# Lightpack_6_0T_man.net
KiCad netlist of a schematic drawn in EAGLE
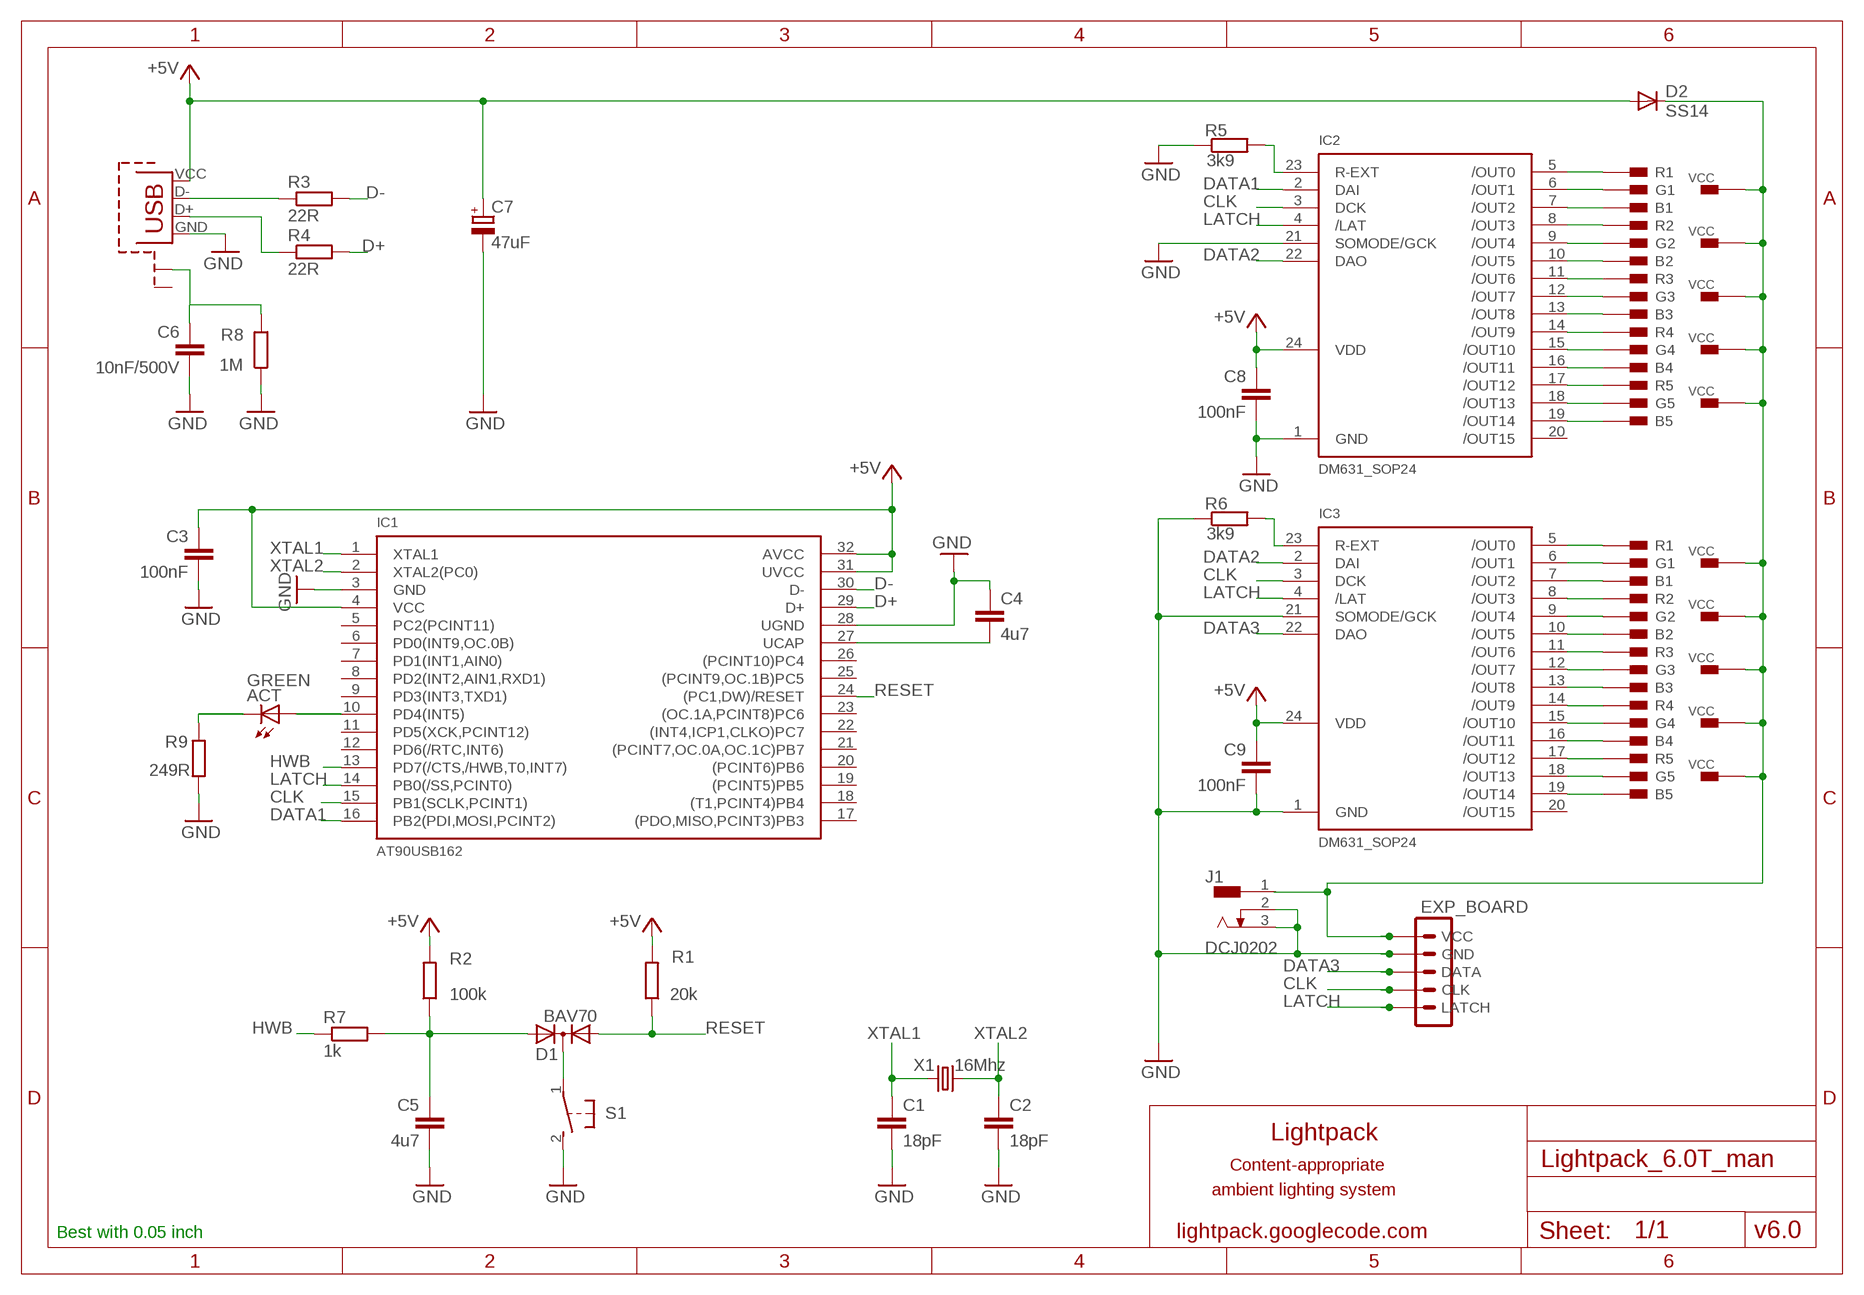
[diagram p0: schematic, sheet 1]

(export (version "E")
  (design (tool "Eeschema 10.0.6"))
  (components
    (comp (ref "ACT")
      (value "GREEN")
      (footprint "eagle-import:LED3MM")
      (libsource (lib "eagle-import") (part "LED3MM"))
    )
    (comp (ref "C1")
      (value "18pF")
      (footprint "eagle-import:C0805")
      (libsource (lib "eagle-import") (part "C-EUC0805"))
    )
    (comp (ref "C2")
      (value "18pF")
      (footprint "eagle-import:C0805")
      (libsource (lib "eagle-import") (part "C-EUC0805"))
    )
    (comp (ref "C3")
      (value "100nF")
      (footprint "eagle-import:C0805")
      (libsource (lib "eagle-import") (part "C-EUC0805"))
    )
    (comp (ref "C4")
      (value "4u7")
      (footprint "eagle-import:C0805")
      (libsource (lib "eagle-import") (part "C-EUC0805"))
    )
    (comp (ref "C5")
      (value "4u7")
      (footprint "eagle-import:C0805")
      (libsource (lib "eagle-import") (part "C-EUC0805"))
    )
    (comp (ref "C6")
      (value "10nF/500V")
      (footprint "eagle-import:C0805")
      (libsource (lib "eagle-import") (part "C-EUC0805"))
    )
    (comp (ref "C7")
      (value "47uF")
      (footprint "eagle-import:SMC_D")
      (libsource (lib "eagle-import") (part "CPOL-EUSMCD"))
    )
    (comp (ref "C8")
      (value "100nF")
      (footprint "eagle-import:C0805")
      (libsource (lib "eagle-import") (part "C-EUC0805"))
    )
    (comp (ref "C9")
      (value "100nF")
      (footprint "eagle-import:C0805")
      (libsource (lib "eagle-import") (part "C-EUC0805"))
    )
    (comp (ref "CN1")
      (value "USB-MICRO-B-EVT")
      (footprint "eagle-import:USB-MICRO-B-UNIVERSAL-SOLID-FOOTS")
      (libsource (lib "eagle-import") (part "USB-MICRO-B-EVT"))
    )
    (comp (ref "CN2")
      (value "RJ11-5P-REEL-LIGHTPACK6T2")
      (footprint "eagle-import:RJ11-1XN-5P")
      (libsource (lib "eagle-import") (part "RJ11-5P-REEL-LIGHTPACK6T2"))
    )
    (comp (ref "CN3")
      (value "RJ11-5P-REEL-MAIN")
      (footprint "eagle-import:RJ11-1XN-5P")
      (libsource (lib "eagle-import") (part "RJ11-5P-REEL-MAIN"))
    )
    (comp (ref "D1")
      (value "BAV70")
      (footprint "eagle-import:SOT23")
      (libsource (lib "eagle-import") (part "DIODE-2AC|CASOT23"))
    )
    (comp (ref "D2")
      (value "SS14")
      (footprint "eagle-import:SMB")
      (libsource (lib "eagle-import") (part "DIODE-SMB"))
    )
    (comp (ref "EXP_BOARD")
      (value "MA05-1")
      (footprint "eagle-import:MA05-1")
      (libsource (lib "eagle-import") (part "MA05-1"))
    )
    (comp (ref "IC1")
      (value "AT90USB162")
      (footprint "eagle-import:TQFP32")
      (libsource (lib "eagle-import") (part "AT90USB162"))
    )
    (comp (ref "IC2")
      (value "DM631_SOP24")
      (footprint "eagle-import:SOP24-300-1.27")
      (libsource (lib "eagle-import") (part "DM631_SOP24"))
    )
    (comp (ref "IC3")
      (value "DM631_SOP24")
      (footprint "eagle-import:SOP24-300-1.27")
      (libsource (lib "eagle-import") (part "DM631_SOP24"))
    )
    (comp (ref "J1")
      (value "DCJ0202")
      (footprint "eagle-import:DCJ0202")
      (libsource (lib "eagle-import") (part "DCJ0202"))
    )
    (comp (ref "R1")
      (value "20k")
      (footprint "eagle-import:R0805")
      (libsource (lib "eagle-import") (part "R-EU_R0805"))
    )
    (comp (ref "R2")
      (value "100k")
      (footprint "eagle-import:R0805")
      (libsource (lib "eagle-import") (part "R-EU_R0805"))
    )
    (comp (ref "R3")
      (value "22R")
      (footprint "eagle-import:R0805")
      (libsource (lib "eagle-import") (part "R-EU_R0805"))
    )
    (comp (ref "R4")
      (value "22R")
      (footprint "eagle-import:R0805")
      (libsource (lib "eagle-import") (part "R-EU_R0805"))
    )
    (comp (ref "R5")
      (value "3k9")
      (footprint "eagle-import:R0805")
      (libsource (lib "eagle-import") (part "R-EU_R0805"))
    )
    (comp (ref "R6")
      (value "3k9")
      (footprint "eagle-import:R0805")
      (libsource (lib "eagle-import") (part "R-EU_R0805"))
    )
    (comp (ref "R7")
      (value "1k")
      (footprint "eagle-import:R0805")
      (libsource (lib "eagle-import") (part "R-EU_R0805"))
    )
    (comp (ref "R8")
      (value "1M")
      (footprint "eagle-import:R0805")
      (libsource (lib "eagle-import") (part "R-EU_R0805"))
    )
    (comp (ref "R9")
      (value "249R")
      (footprint "eagle-import:R0805")
      (libsource (lib "eagle-import") (part "R-EU_R0805"))
    )
    (comp (ref "S1")
      (value "31-XX")
      (footprint "eagle-import:B3F-31XX")
      (libsource (lib "eagle-import") (part "31-XX"))
    )
    (comp (ref "X1")
      (value "16Mhz")
      (footprint "eagle-import:HC49UP")
      (libsource (lib "eagle-import") (part "CRYSTALHC49UP"))
    )
  )
  (nets
    (net (code "1") (name "+5V") (class "Default")
      (node (ref "C3") (pin "1") (pinfunction "1_1") (pintype "passive"))
      (node (ref "C7") (pin "+") (pinfunction "+_+") (pintype "passive"))
      (node (ref "C8") (pin "1") (pinfunction "1_1") (pintype "passive"))
      (node (ref "C9") (pin "1") (pinfunction "1_1") (pintype "passive"))
      (node (ref "CN1") (pin "VCC") (pinfunction "VBUS_VCC") (pintype "bidirectional"))
      (node (ref "D2") (pin "A") (pinfunction "A_A") (pintype "passive"))
      (node (ref "IC1") (pin "31") (pinfunction "UVCC_31") (pintype "bidirectional"))
      (node (ref "IC1") (pin "32") (pinfunction "AVCC_32") (pintype "bidirectional"))
      (node (ref "IC1") (pin "4") (pinfunction "VCC_4") (pintype "bidirectional"))
      (node (ref "IC2") (pin "24") (pinfunction "VDD_24") (pintype "bidirectional"))
      (node (ref "IC3") (pin "24") (pinfunction "VDD_24") (pintype "bidirectional"))
      (node (ref "R1") (pin "2") (pinfunction "2_2") (pintype "passive"))
      (node (ref "R2") (pin "2") (pinfunction "2_2") (pintype "passive"))
    )
    (net (code "2") (name "/CLK") (class "Default")
      (node (ref "EXP_BOARD") (pin "2") (pinfunction "CLK_2") (pintype "passive"))
      (node (ref "IC1") (pin "15") (pinfunction "PB1(SCLK,PCINT1)_15") (pintype "bidirectional"))
      (node (ref "IC2") (pin "3") (pinfunction "DCK_3") (pintype "bidirectional"))
      (node (ref "IC3") (pin "3") (pinfunction "DCK_3") (pintype "bidirectional"))
    )
    (net (code "3") (name "/D+") (class "Default")
      (node (ref "IC1") (pin "29") (pinfunction "D+_29") (pintype "bidirectional"))
      (node (ref "R4") (pin "2") (pinfunction "2_2") (pintype "passive"))
    )
    (net (code "4") (name "/D-") (class "Default")
      (node (ref "IC1") (pin "30") (pinfunction "D-_30") (pintype "bidirectional"))
      (node (ref "R3") (pin "2") (pinfunction "2_2") (pintype "passive"))
    )
    (net (code "5") (name "/DATA1") (class "Default")
      (node (ref "IC1") (pin "16") (pinfunction "PB2(PDI,MOSI,PCINT2)_16") (pintype "bidirectional"))
      (node (ref "IC2") (pin "2") (pinfunction "DAI_2") (pintype "bidirectional"))
    )
    (net (code "6") (name "/DATA2") (class "Default")
      (node (ref "IC2") (pin "22") (pinfunction "DAO_22") (pintype "bidirectional"))
      (node (ref "IC3") (pin "2") (pinfunction "DAI_2") (pintype "bidirectional"))
    )
    (net (code "7") (name "/DATA3") (class "Default")
      (node (ref "EXP_BOARD") (pin "3") (pinfunction "DATA_3") (pintype "passive"))
      (node (ref "IC3") (pin "22") (pinfunction "DAO_22") (pintype "bidirectional"))
    )
    (net (code "8") (name "/HWB") (class "Default")
      (node (ref "IC1") (pin "13") (pinfunction "PD7(/CTS,/HWB,T0,INT7)_13") (pintype "bidirectional"))
      (node (ref "R7") (pin "1") (pinfunction "1_1") (pintype "passive"))
    )
    (net (code "9") (name "/LATCH") (class "Default")
      (node (ref "EXP_BOARD") (pin "1") (pinfunction "LATCH_1") (pintype "passive"))
      (node (ref "IC1") (pin "14") (pinfunction "PB0(/SS,PCINT0)_14") (pintype "bidirectional"))
      (node (ref "IC2") (pin "4") (pinfunction "/LAT_4") (pintype "bidirectional"))
      (node (ref "IC3") (pin "4") (pinfunction "/LAT_4") (pintype "bidirectional"))
    )
    (net (code "10") (name "/RESET") (class "Default")
      (node (ref "D1") (pin "1") (pinfunction "A1_1") (pintype "passive"))
      (node (ref "IC1") (pin "24") (pinfunction "(PC1,DW)/RESET_24") (pintype "bidirectional"))
      (node (ref "R1") (pin "1") (pinfunction "1_1") (pintype "passive"))
    )
    (net (code "11") (name "/XTAL1") (class "Default")
      (node (ref "C1") (pin "1") (pinfunction "1_1") (pintype "passive"))
      (node (ref "IC1") (pin "1") (pinfunction "XTAL1_1") (pintype "bidirectional"))
      (node (ref "X1") (pin "1") (pinfunction "1_1") (pintype "passive"))
    )
    (net (code "12") (name "/XTAL2") (class "Default")
      (node (ref "C2") (pin "1") (pinfunction "1_1") (pintype "passive"))
      (node (ref "IC1") (pin "2") (pinfunction "XTAL2(PC0)_2") (pintype "bidirectional"))
      (node (ref "X1") (pin "2") (pinfunction "2_2") (pintype "passive"))
    )
    (net (code "13") (name "GND") (class "Default")
      (node (ref "C1") (pin "2") (pinfunction "2_2") (pintype "passive"))
      (node (ref "C2") (pin "2") (pinfunction "2_2") (pintype "passive"))
      (node (ref "C3") (pin "2") (pinfunction "2_2") (pintype "passive"))
      (node (ref "C4") (pin "1") (pinfunction "1_1") (pintype "passive"))
      (node (ref "C5") (pin "2") (pinfunction "2_2") (pintype "passive"))
      (node (ref "C6") (pin "1") (pinfunction "1_1") (pintype "passive"))
      (node (ref "C7") (pin "-") (pinfunction "-_-") (pintype "passive"))
      (node (ref "C8") (pin "2") (pinfunction "2_2") (pintype "passive"))
      (node (ref "C9") (pin "2") (pinfunction "2_2") (pintype "passive"))
      (node (ref "CN1") (pin "GND") (pinfunction "GND_GND") (pintype "bidirectional"))
      (node (ref "EXP_BOARD") (pin "4") (pinfunction "GND_4") (pintype "passive"))
      (node (ref "IC1") (pin "28") (pinfunction "UGND_28") (pintype "bidirectional"))
      (node (ref "IC1") (pin "3") (pinfunction "GND_3") (pintype "bidirectional"))
      (node (ref "IC2") (pin "1") (pinfunction "GND_1") (pintype "bidirectional"))
      (node (ref "IC2") (pin "21") (pinfunction "SOMODE/GCK_21") (pintype "bidirectional"))
      (node (ref "IC3") (pin "1") (pinfunction "GND_1") (pintype "bidirectional"))
      (node (ref "IC3") (pin "21") (pinfunction "SOMODE/GCK_21") (pintype "bidirectional"))
      (node (ref "J1") (pin "2") (pinfunction "2_2") (pintype "passive"))
      (node (ref "J1") (pin "3") (pinfunction "3_3") (pintype "passive"))
      (node (ref "R5") (pin "1") (pinfunction "1_1") (pintype "passive"))
      (node (ref "R6") (pin "1") (pinfunction "1_1") (pintype "passive"))
      (node (ref "R8") (pin "1") (pinfunction "1_1") (pintype "passive"))
      (node (ref "R9") (pin "1") (pinfunction "1_1") (pintype "passive"))
      (node (ref "S1") (pin "2") (pinfunction "S_2") (pintype "passive"))
    )
    (net (code "14") (name "Net-(ACT-C)") (class "Default")
      (node (ref "ACT") (pin "K") (pinfunction "C_K") (pintype "passive"))
      (node (ref "R9") (pin "2") (pinfunction "2_2") (pintype "passive"))
    )
    (net (code "15") (name "Net-(CN1-PadD+)") (class "Default")
      (node (ref "CN1") (pin "D+") (pinfunction "D+_D+") (pintype "bidirectional"))
      (node (ref "R4") (pin "1") (pinfunction "1_1") (pintype "passive"))
    )
    (net (code "16") (name "Net-(CN1-PadD-)") (class "Default")
      (node (ref "CN1") (pin "D-") (pinfunction "D-_D-") (pintype "bidirectional"))
      (node (ref "R3") (pin "1") (pinfunction "1_1") (pintype "passive"))
    )
    (net (code "17") (name "Net-(CN1-SHIELD1)") (class "Default")
      (node (ref "C6") (pin "2") (pinfunction "2_2") (pintype "passive"))
      (node (ref "CN1") (pin "P$4") (pinfunction "SHIELD1_P$4") (pintype "bidirectional"))
      (node (ref "R8") (pin "2") (pinfunction "2_2") (pintype "passive"))
    )
    (net (code "18") (name "Net-(CN2-B1)") (class "Default")
      (node (ref "CN2") (pin "B5") (pinfunction "B1_B5") (pintype "bidirectional"))
      (node (ref "IC2") (pin "7") (pinfunction "/OUT2_7") (pintype "bidirectional"))
    )
    (net (code "19") (name "Net-(CN2-B2)") (class "Default")
      (node (ref "CN2") (pin "B4") (pinfunction "B2_B4") (pintype "bidirectional"))
      (node (ref "IC2") (pin "10") (pinfunction "/OUT5_10") (pintype "bidirectional"))
    )
    (net (code "20") (name "Net-(CN2-B3)") (class "Default")
      (node (ref "CN2") (pin "B1") (pinfunction "B3_B1") (pintype "bidirectional"))
      (node (ref "IC2") (pin "13") (pinfunction "/OUT8_13") (pintype "bidirectional"))
    )
    (net (code "21") (name "Net-(CN2-B4)") (class "Default")
      (node (ref "CN2") (pin "B2") (pinfunction "B4_B2") (pintype "bidirectional"))
      (node (ref "IC2") (pin "16") (pinfunction "/OUT11_16") (pintype "bidirectional"))
    )
    (net (code "22") (name "Net-(CN2-B5)") (class "Default")
      (node (ref "CN2") (pin "B3") (pinfunction "B5_B3") (pintype "bidirectional"))
      (node (ref "IC2") (pin "19") (pinfunction "/OUT14_19") (pintype "bidirectional"))
    )
    (net (code "23") (name "Net-(CN2-G1)") (class "Default")
      (node (ref "CN2") (pin "G5") (pinfunction "G1_G5") (pintype "bidirectional"))
      (node (ref "IC2") (pin "6") (pinfunction "/OUT1_6") (pintype "bidirectional"))
    )
    (net (code "24") (name "Net-(CN2-G2)") (class "Default")
      (node (ref "CN2") (pin "G4") (pinfunction "G2_G4") (pintype "bidirectional"))
      (node (ref "IC2") (pin "9") (pinfunction "/OUT4_9") (pintype "bidirectional"))
    )
    (net (code "25") (name "Net-(CN2-G3)") (class "Default")
      (node (ref "CN2") (pin "G1") (pinfunction "G3_G1") (pintype "bidirectional"))
      (node (ref "IC2") (pin "12") (pinfunction "/OUT7_12") (pintype "bidirectional"))
    )
    (net (code "26") (name "Net-(CN2-G4)") (class "Default")
      (node (ref "CN2") (pin "G2") (pinfunction "G4_G2") (pintype "bidirectional"))
      (node (ref "IC2") (pin "15") (pinfunction "/OUT10_15") (pintype "bidirectional"))
    )
    (net (code "27") (name "Net-(CN2-G5)") (class "Default")
      (node (ref "CN2") (pin "G3") (pinfunction "G5_G3") (pintype "bidirectional"))
      (node (ref "IC2") (pin "18") (pinfunction "/OUT13_18") (pintype "bidirectional"))
    )
    (net (code "28") (name "Net-(CN2-R1)") (class "Default")
      (node (ref "CN2") (pin "R5") (pinfunction "R1_R5") (pintype "bidirectional"))
      (node (ref "IC2") (pin "5") (pinfunction "/OUT0_5") (pintype "bidirectional"))
    )
    (net (code "29") (name "Net-(CN2-R2)") (class "Default")
      (node (ref "CN2") (pin "R4") (pinfunction "R2_R4") (pintype "bidirectional"))
      (node (ref "IC2") (pin "8") (pinfunction "/OUT3_8") (pintype "bidirectional"))
    )
    (net (code "30") (name "Net-(CN2-R3)") (class "Default")
      (node (ref "CN2") (pin "R1") (pinfunction "R3_R1") (pintype "bidirectional"))
      (node (ref "IC2") (pin "11") (pinfunction "/OUT6_11") (pintype "bidirectional"))
    )
    (net (code "31") (name "Net-(CN2-R4)") (class "Default")
      (node (ref "CN2") (pin "R2") (pinfunction "R4_R2") (pintype "bidirectional"))
      (node (ref "IC2") (pin "14") (pinfunction "/OUT9_14") (pintype "bidirectional"))
    )
    (net (code "32") (name "Net-(CN2-R5)") (class "Default")
      (node (ref "CN2") (pin "R3") (pinfunction "R5_R3") (pintype "bidirectional"))
      (node (ref "IC2") (pin "17") (pinfunction "/OUT12_17") (pintype "bidirectional"))
    )
    (net (code "33") (name "Net-(CN2-VCC1)") (class "Default")
      (node (ref "CN2") (pin "VCC1") (pinfunction "VCC3_VCC1") (pintype "bidirectional"))
      (node (ref "CN2") (pin "VCC2") (pinfunction "VCC4_VCC2") (pintype "bidirectional"))
      (node (ref "CN2") (pin "VCC3") (pinfunction "VCC5_VCC3") (pintype "bidirectional"))
      (node (ref "CN2") (pin "VCC4") (pinfunction "VCC2_VCC4") (pintype "bidirectional"))
      (node (ref "CN2") (pin "VCC5") (pinfunction "VCC1_VCC5") (pintype "bidirectional"))
      (node (ref "CN3") (pin "VCC1") (pinfunction "VCC1_VCC1") (pintype "bidirectional"))
      (node (ref "CN3") (pin "VCC2") (pinfunction "VCC2_VCC2") (pintype "bidirectional"))
      (node (ref "CN3") (pin "VCC3") (pinfunction "VCC3_VCC3") (pintype "bidirectional"))
      (node (ref "CN3") (pin "VCC4") (pinfunction "VCC4_VCC4") (pintype "bidirectional"))
      (node (ref "CN3") (pin "VCC5") (pinfunction "VCC5_VCC5") (pintype "bidirectional"))
      (node (ref "D2") (pin "C") (pinfunction "C_C") (pintype "passive"))
      (node (ref "EXP_BOARD") (pin "5") (pinfunction "VCC_5") (pintype "passive"))
      (node (ref "J1") (pin "1") (pinfunction "1_1") (pintype "passive"))
    )
    (net (code "34") (name "Net-(D1-A2)") (class "Default")
      (node (ref "C5") (pin "1") (pinfunction "1_1") (pintype "passive"))
      (node (ref "D1") (pin "2") (pinfunction "A2_2") (pintype "passive"))
      (node (ref "R2") (pin "1") (pinfunction "1_1") (pintype "passive"))
      (node (ref "R7") (pin "2") (pinfunction "2_2") (pintype "passive"))
    )
    (net (code "35") (name "Net-(D1-C)") (class "Default")
      (node (ref "D1") (pin "3") (pinfunction "C_3") (pintype "passive"))
      (node (ref "S1") (pin "1") (pinfunction "P_1") (pintype "passive"))
    )
    (net (code "36") (name "Net-(IC1-PD4(INT5))") (class "Default")
      (node (ref "ACT") (pin "A") (pinfunction "A_A") (pintype "passive"))
      (node (ref "IC1") (pin "10") (pinfunction "PD4(INT5)_10") (pintype "bidirectional"))
    )
    (net (code "37") (name "Net-(IC1-UCAP)") (class "Default")
      (node (ref "C4") (pin "2") (pinfunction "2_2") (pintype "passive"))
      (node (ref "IC1") (pin "27") (pinfunction "UCAP_27") (pintype "bidirectional"))
    )
    (net (code "38") (name "Net-(IC2-R-EXT)") (class "Default")
      (node (ref "IC2") (pin "23") (pinfunction "R-EXT_23") (pintype "bidirectional"))
      (node (ref "R5") (pin "2") (pinfunction "2_2") (pintype "passive"))
    )
    (net (code "39") (name "Net-(IC3-R-EXT)") (class "Default")
      (node (ref "IC3") (pin "23") (pinfunction "R-EXT_23") (pintype "bidirectional"))
      (node (ref "R6") (pin "2") (pinfunction "2_2") (pintype "passive"))
    )
    (net (code "40") (name "Net-(IC3-{slash}OUT0)") (class "Default")
      (node (ref "CN3") (pin "R1") (pinfunction "R1_R1") (pintype "bidirectional"))
      (node (ref "IC3") (pin "5") (pinfunction "/OUT0_5") (pintype "bidirectional"))
    )
    (net (code "41") (name "Net-(IC3-{slash}OUT1)") (class "Default")
      (node (ref "CN3") (pin "G1") (pinfunction "G1_G1") (pintype "bidirectional"))
      (node (ref "IC3") (pin "6") (pinfunction "/OUT1_6") (pintype "bidirectional"))
    )
    (net (code "42") (name "Net-(IC3-{slash}OUT2)") (class "Default")
      (node (ref "CN3") (pin "B1") (pinfunction "B1_B1") (pintype "bidirectional"))
      (node (ref "IC3") (pin "7") (pinfunction "/OUT2_7") (pintype "bidirectional"))
    )
    (net (code "43") (name "Net-(IC3-{slash}OUT3)") (class "Default")
      (node (ref "CN3") (pin "R2") (pinfunction "R2_R2") (pintype "bidirectional"))
      (node (ref "IC3") (pin "8") (pinfunction "/OUT3_8") (pintype "bidirectional"))
    )
    (net (code "44") (name "Net-(IC3-{slash}OUT4)") (class "Default")
      (node (ref "CN3") (pin "G2") (pinfunction "G2_G2") (pintype "bidirectional"))
      (node (ref "IC3") (pin "9") (pinfunction "/OUT4_9") (pintype "bidirectional"))
    )
    (net (code "45") (name "Net-(IC3-{slash}OUT5)") (class "Default")
      (node (ref "CN3") (pin "B2") (pinfunction "B2_B2") (pintype "bidirectional"))
      (node (ref "IC3") (pin "10") (pinfunction "/OUT5_10") (pintype "bidirectional"))
    )
    (net (code "46") (name "Net-(IC3-{slash}OUT6)") (class "Default")
      (node (ref "CN3") (pin "R3") (pinfunction "R3_R3") (pintype "bidirectional"))
      (node (ref "IC3") (pin "11") (pinfunction "/OUT6_11") (pintype "bidirectional"))
    )
    (net (code "47") (name "Net-(IC3-{slash}OUT7)") (class "Default")
      (node (ref "CN3") (pin "G3") (pinfunction "G3_G3") (pintype "bidirectional"))
      (node (ref "IC3") (pin "12") (pinfunction "/OUT7_12") (pintype "bidirectional"))
    )
    (net (code "48") (name "Net-(IC3-{slash}OUT8)") (class "Default")
      (node (ref "CN3") (pin "B3") (pinfunction "B3_B3") (pintype "bidirectional"))
      (node (ref "IC3") (pin "13") (pinfunction "/OUT8_13") (pintype "bidirectional"))
    )
    (net (code "49") (name "Net-(IC3-{slash}OUT9)") (class "Default")
      (node (ref "CN3") (pin "R4") (pinfunction "R4_R4") (pintype "bidirectional"))
      (node (ref "IC3") (pin "14") (pinfunction "/OUT9_14") (pintype "bidirectional"))
    )
    (net (code "50") (name "Net-(IC3-{slash}OUT10)") (class "Default")
      (node (ref "CN3") (pin "G4") (pinfunction "G4_G4") (pintype "bidirectional"))
      (node (ref "IC3") (pin "15") (pinfunction "/OUT10_15") (pintype "bidirectional"))
    )
    (net (code "51") (name "Net-(IC3-{slash}OUT11)") (class "Default")
      (node (ref "CN3") (pin "B4") (pinfunction "B4_B4") (pintype "bidirectional"))
      (node (ref "IC3") (pin "16") (pinfunction "/OUT11_16") (pintype "bidirectional"))
    )
    (net (code "52") (name "Net-(IC3-{slash}OUT12)") (class "Default")
      (node (ref "CN3") (pin "R5") (pinfunction "R5_R5") (pintype "bidirectional"))
      (node (ref "IC3") (pin "17") (pinfunction "/OUT12_17") (pintype "bidirectional"))
    )
    (net (code "53") (name "Net-(IC3-{slash}OUT13)") (class "Default")
      (node (ref "CN3") (pin "G5") (pinfunction "G5_G5") (pintype "bidirectional"))
      (node (ref "IC3") (pin "18") (pinfunction "/OUT13_18") (pintype "bidirectional"))
    )
    (net (code "54") (name "Net-(IC3-{slash}OUT14)") (class "Default")
      (node (ref "CN3") (pin "B5") (pinfunction "B5_B5") (pintype "bidirectional"))
      (node (ref "IC3") (pin "19") (pinfunction "/OUT14_19") (pintype "bidirectional"))
    )
    (net (code "55") (name "unconnected-(CN1-SHIELD2-PadP$1)") (class "Default")
      (node (ref "CN1") (pin "P$1") (pinfunction "SHIELD2_P$1") (pintype "bidirectional"))
    )
    (net (code "56") (name "unconnected-(IC1-(INT4,ICP1,CLKO)PC7-Pad22)") (class "Default")
      (node (ref "IC1") (pin "22") (pinfunction "(INT4,ICP1,CLKO)PC7_22") (pintype "bidirectional"))
    )
    (net (code "57") (name "unconnected-(IC1-(OC.1A,PCINT8)PC6-Pad23)") (class "Default")
      (node (ref "IC1") (pin "23") (pinfunction "(OC.1A,PCINT8)PC6_23") (pintype "bidirectional"))
    )
    (net (code "58") (name "unconnected-(IC1-(PCINT5)PB5-Pad19)") (class "Default")
      (node (ref "IC1") (pin "19") (pinfunction "(PCINT5)PB5_19") (pintype "bidirectional"))
    )
    (net (code "59") (name "unconnected-(IC1-(PCINT6)PB6-Pad20)") (class "Default")
      (node (ref "IC1") (pin "20") (pinfunction "(PCINT6)PB6_20") (pintype "bidirectional"))
    )
    (net (code "60") (name "unconnected-(IC1-(PCINT7,OC.0A,OC.1C)PB7-Pad21)") (class "Default")
      (node (ref "IC1") (pin "21") (pinfunction "(PCINT7,OC.0A,OC.1C)PB7_21") (pintype "bidirectional"))
    )
    (net (code "61") (name "unconnected-(IC1-(PCINT9,OC.1B)PC5-Pad25)") (class "Default")
      (node (ref "IC1") (pin "25") (pinfunction "(PCINT9,OC.1B)PC5_25") (pintype "bidirectional"))
    )
    (net (code "62") (name "unconnected-(IC1-(PCINT10)PC4-Pad26)") (class "Default")
      (node (ref "IC1") (pin "26") (pinfunction "(PCINT10)PC4_26") (pintype "bidirectional"))
    )
    (net (code "63") (name "unconnected-(IC1-(PDO,MISO,PCINT3)PB3-Pad17)") (class "Default")
      (node (ref "IC1") (pin "17") (pinfunction "(PDO,MISO,PCINT3)PB3_17") (pintype "bidirectional"))
    )
    (net (code "64") (name "unconnected-(IC1-(T1,PCINT4)PB4-Pad18)") (class "Default")
      (node (ref "IC1") (pin "18") (pinfunction "(T1,PCINT4)PB4_18") (pintype "bidirectional"))
    )
    (net (code "65") (name "unconnected-(IC1-PC2(PCINT11)-Pad5)") (class "Default")
      (node (ref "IC1") (pin "5") (pinfunction "PC2(PCINT11)_5") (pintype "bidirectional"))
    )
    (net (code "66") (name "unconnected-(IC1-PD0(INT9,OC.0B)-Pad6)") (class "Default")
      (node (ref "IC1") (pin "6") (pinfunction "PD0(INT9,OC.0B)_6") (pintype "bidirectional"))
    )
    (net (code "67") (name "unconnected-(IC1-PD1(INT1,AIN0)-Pad7)") (class "Default")
      (node (ref "IC1") (pin "7") (pinfunction "PD1(INT1,AIN0)_7") (pintype "bidirectional"))
    )
    (net (code "68") (name "unconnected-(IC1-PD2(INT2,AIN1,RXD1)-Pad8)") (class "Default")
      (node (ref "IC1") (pin "8") (pinfunction "PD2(INT2,AIN1,RXD1)_8") (pintype "bidirectional"))
    )
    (net (code "69") (name "unconnected-(IC1-PD3(INT3,TXD1)-Pad9)") (class "Default")
      (node (ref "IC1") (pin "9") (pinfunction "PD3(INT3,TXD1)_9") (pintype "bidirectional"))
    )
    (net (code "70") (name "unconnected-(IC1-PD5(XCK,PCINT12)-Pad11)") (class "Default")
      (node (ref "IC1") (pin "11") (pinfunction "PD5(XCK,PCINT12)_11") (pintype "bidirectional"))
    )
    (net (code "71") (name "unconnected-(IC1-PD6({slash}RTC,INT6)-Pad12)") (class "Default")
      (node (ref "IC1") (pin "12") (pinfunction "PD6(/RTC,INT6)_12") (pintype "bidirectional"))
    )
    (net (code "72") (name "unconnected-(IC2-{slash}OUT15-Pad20)") (class "Default")
      (node (ref "IC2") (pin "20") (pinfunction "/OUT15_20") (pintype "bidirectional"))
    )
    (net (code "73") (name "unconnected-(IC3-{slash}OUT15-Pad20)") (class "Default")
      (node (ref "IC3") (pin "20") (pinfunction "/OUT15_20") (pintype "bidirectional"))
    )
  )
)
